# th.net
KiCad netlist of a schematic drawn in EAGLE
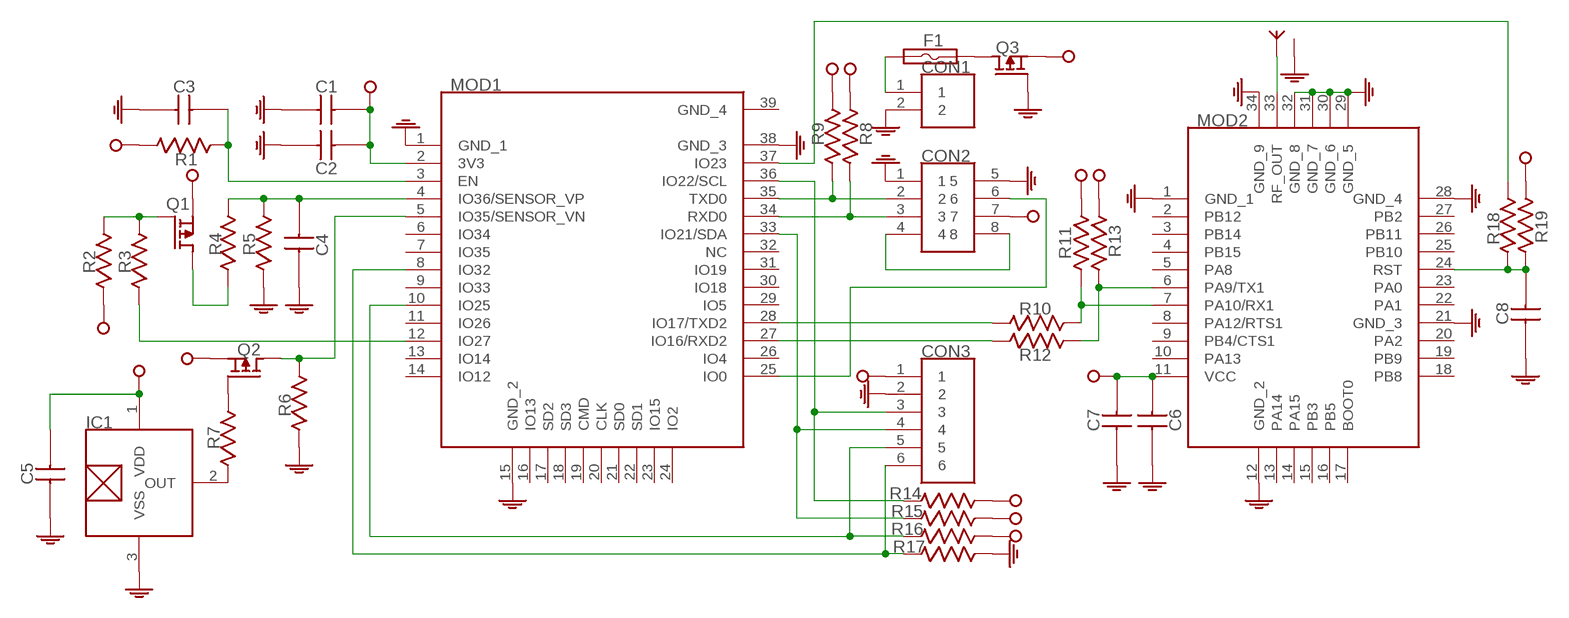
[diagram p0: schematic, sheet 1]

(export (version "E")
  (design (tool "Eeschema 10.0.6"))
  (components
    (comp (ref "ANT1")
      (value "SMA-RF")
      (footprint "eagle-import:SMA-RF")
      (libsource (lib "eagle-import") (part "SMA-RF"))
    )
    (comp (ref "C1")
      (value "CAPACITOR-0805")
      (footprint "eagle-import:0805")
      (libsource (lib "eagle-import") (part "CAPACITOR-0805"))
    )
    (comp (ref "C2")
      (value "CAPACITOR-0603")
      (footprint "eagle-import:0603")
      (libsource (lib "eagle-import") (part "CAPACITOR-0603"))
    )
    (comp (ref "C3")
      (value "CAPACITOR-0603")
      (footprint "eagle-import:0603")
      (libsource (lib "eagle-import") (part "CAPACITOR-0603"))
    )
    (comp (ref "C4")
      (value "CAPACITOR-0603")
      (footprint "eagle-import:0603")
      (libsource (lib "eagle-import") (part "CAPACITOR-0603"))
    )
    (comp (ref "C5")
      (value "CAPACITOR-0603")
      (footprint "eagle-import:0603")
      (libsource (lib "eagle-import") (part "CAPACITOR-0603"))
    )
    (comp (ref "C6")
      (value "CAPACITOR-0805")
      (footprint "eagle-import:0805")
      (libsource (lib "eagle-import") (part "CAPACITOR-0805"))
    )
    (comp (ref "C7")
      (value "CAPACITOR-0603")
      (footprint "eagle-import:0603")
      (libsource (lib "eagle-import") (part "CAPACITOR-0603"))
    )
    (comp (ref "C8")
      (value "CAPACITOR-0603")
      (footprint "eagle-import:0603")
      (libsource (lib "eagle-import") (part "CAPACITOR-0603"))
    )
    (comp (ref "CON1")
      (value "JST-PH-2-2.0MM")
      (footprint "eagle-import:JST-PH-2-2.0MM")
      (libsource (lib "eagle-import") (part "JST-PH-2-2.0MM"))
    )
    (comp (ref "CON2")
      (value "HEADER-8P-2R-DIP-2_0MM")
      (footprint "eagle-import:HEADER-8P-2R-DIP-2_0MM")
      (libsource (lib "eagle-import") (part "HEADER-8P-2R-DIP-2_0MM"))
    )
    (comp (ref "CON3")
      (value "CON-6P-3_81-PLUG")
      (footprint "eagle-import:CON-6P-3_81-PLUG")
      (libsource (lib "eagle-import") (part "CON-6P-3_81-PLUG"))
    )
    (comp (ref "F1")
      (value "FUSE-0805")
      (footprint "eagle-import:0805")
      (libsource (lib "eagle-import") (part "FUSE-0805"))
    )
    (comp (ref "IC1")
      (value "S-5712-SOT23-3")
      (footprint "eagle-import:SOT23-3")
      (libsource (lib "eagle-import") (part "S-5712-SOT23-3"))
    )
    (comp (ref "MOD1")
      (value "ESP32-WROOM-32D")
      (footprint "eagle-import:ESP32-WROOM-32D")
      (libsource (lib "eagle-import") (part "ESP32-WROOM-32D"))
    )
    (comp (ref "MOD2")
      (value "RAK811")
      (footprint "eagle-import:RAK811")
      (libsource (lib "eagle-import") (part "RAK811"))
    )
    (comp (ref "Q1")
      (value "P-MOSFET")
      (footprint "eagle-import:SOT23-3")
      (libsource (lib "eagle-import") (part "P-MOSFET"))
    )
    (comp (ref "Q2")
      (value "P-MOSFET")
      (footprint "eagle-import:SOT23-3")
      (libsource (lib "eagle-import") (part "P-MOSFET"))
    )
    (comp (ref "Q3")
      (value "P-MOSFET")
      (footprint "eagle-import:SOT23-3")
      (libsource (lib "eagle-import") (part "P-MOSFET"))
    )
    (comp (ref "R1")
      (value "RESISTOR-0603")
      (footprint "eagle-import:0603")
      (libsource (lib "eagle-import") (part "RESISTOR-0603"))
    )
    (comp (ref "R2")
      (value "RESISTOR-0603")
      (footprint "eagle-import:0603")
      (libsource (lib "eagle-import") (part "RESISTOR-0603"))
    )
    (comp (ref "R3")
      (value "RESISTOR-0603")
      (footprint "eagle-import:0603")
      (libsource (lib "eagle-import") (part "RESISTOR-0603"))
    )
    (comp (ref "R4")
      (value "RESISTOR-0603")
      (footprint "eagle-import:0603")
      (libsource (lib "eagle-import") (part "RESISTOR-0603"))
    )
    (comp (ref "R5")
      (value "RESISTOR-0603")
      (footprint "eagle-import:0603")
      (libsource (lib "eagle-import") (part "RESISTOR-0603"))
    )
    (comp (ref "R6")
      (value "RESISTOR-0603")
      (footprint "eagle-import:0603")
      (libsource (lib "eagle-import") (part "RESISTOR-0603"))
    )
    (comp (ref "R7")
      (value "RESISTOR-0603")
      (footprint "eagle-import:0603")
      (libsource (lib "eagle-import") (part "RESISTOR-0603"))
    )
    (comp (ref "R8")
      (value "RESISTOR-0603")
      (footprint "eagle-import:0603")
      (libsource (lib "eagle-import") (part "RESISTOR-0603"))
    )
    (comp (ref "R9")
      (value "RESISTOR-0603")
      (footprint "eagle-import:0603")
      (libsource (lib "eagle-import") (part "RESISTOR-0603"))
    )
    (comp (ref "R10")
      (value "RESISTOR-0603")
      (footprint "eagle-import:0603")
      (libsource (lib "eagle-import") (part "RESISTOR-0603"))
    )
    (comp (ref "R11")
      (value "RESISTOR-0603")
      (footprint "eagle-import:0603")
      (libsource (lib "eagle-import") (part "RESISTOR-0603"))
    )
    (comp (ref "R12")
      (value "RESISTOR-0603")
      (footprint "eagle-import:0603")
      (libsource (lib "eagle-import") (part "RESISTOR-0603"))
    )
    (comp (ref "R13")
      (value "RESISTOR-0603")
      (footprint "eagle-import:0603")
      (libsource (lib "eagle-import") (part "RESISTOR-0603"))
    )
    (comp (ref "R14")
      (value "RESISTOR-0603")
      (footprint "eagle-import:0603")
      (libsource (lib "eagle-import") (part "RESISTOR-0603"))
    )
    (comp (ref "R15")
      (value "RESISTOR-0603")
      (footprint "eagle-import:0603")
      (libsource (lib "eagle-import") (part "RESISTOR-0603"))
    )
    (comp (ref "R16")
      (value "RESISTOR-0603")
      (footprint "eagle-import:0603")
      (libsource (lib "eagle-import") (part "RESISTOR-0603"))
    )
    (comp (ref "R17")
      (value "RESISTOR-0603")
      (footprint "eagle-import:0603")
      (libsource (lib "eagle-import") (part "RESISTOR-0603"))
    )
    (comp (ref "R18")
      (value "RESISTOR-0603")
      (footprint "eagle-import:0603")
      (libsource (lib "eagle-import") (part "RESISTOR-0603"))
    )
    (comp (ref "R19")
      (value "RESISTOR-0603")
      (footprint "eagle-import:0603")
      (libsource (lib "eagle-import") (part "RESISTOR-0603"))
    )
  )
  (nets
    (net (code "1") (name "/GND_4") (class "Default")
      (node (ref "MOD1") (pin "39") (pinfunction "GND_4_39") (pintype "power_in"))
    )
    (net (code "2") (name "GND") (class "Default")
      (node (ref "ANT1") (pin "2") (pinfunction "GND_2") (pintype "power_in"))
      (node (ref "ANT1") (pin "3") (pinfunction "GND_3") (pintype "power_in"))
      (node (ref "ANT1") (pin "4") (pinfunction "GND_4") (pintype "power_in"))
      (node (ref "ANT1") (pin "5") (pinfunction "GND_5") (pintype "power_in"))
      (node (ref "C1") (pin "1") (pinfunction "1_1") (pintype "passive"))
      (node (ref "C2") (pin "1") (pinfunction "1_1") (pintype "passive"))
      (node (ref "C3") (pin "1") (pinfunction "1_1") (pintype "passive"))
      (node (ref "C4") (pin "1") (pinfunction "1_1") (pintype "passive"))
      (node (ref "C5") (pin "1") (pinfunction "1_1") (pintype "passive"))
      (node (ref "C6") (pin "1") (pinfunction "1_1") (pintype "passive"))
      (node (ref "C7") (pin "1") (pinfunction "1_1") (pintype "passive"))
      (node (ref "C8") (pin "1") (pinfunction "1_1") (pintype "passive"))
      (node (ref "CON1") (pin "2") (pinfunction "2_2") (pintype "bidirectional"))
      (node (ref "CON2") (pin "1") (pinfunction "1_1") (pintype "bidirectional"))
      (node (ref "CON2") (pin "5") (pinfunction "5_5") (pintype "bidirectional"))
      (node (ref "CON3") (pin "2") (pinfunction "2_2") (pintype "bidirectional"))
      (node (ref "IC1") (pin "3") (pinfunction "VSS_3") (pintype "power_in"))
      (node (ref "MOD1") (pin "1") (pinfunction "GND_1_1") (pintype "power_in"))
      (node (ref "MOD1") (pin "15") (pinfunction "GND_2_15") (pintype "power_in"))
      (node (ref "MOD1") (pin "38") (pinfunction "GND_3_38") (pintype "power_in"))
      (node (ref "MOD2") (pin "1") (pinfunction "GND_1_1") (pintype "power_in"))
      (node (ref "MOD2") (pin "12") (pinfunction "GND_2_12") (pintype "power_in"))
      (node (ref "MOD2") (pin "21") (pinfunction "GND_3_21") (pintype "power_in"))
      (node (ref "MOD2") (pin "28") (pinfunction "GND_4_28") (pintype "power_in"))
      (node (ref "MOD2") (pin "29") (pinfunction "GND_5_29") (pintype "power_in"))
      (node (ref "MOD2") (pin "30") (pinfunction "GND_6_30") (pintype "power_in"))
      (node (ref "MOD2") (pin "31") (pinfunction "GND_7_31") (pintype "power_in"))
      (node (ref "MOD2") (pin "32") (pinfunction "GND_8_32") (pintype "power_in"))
      (node (ref "MOD2") (pin "34") (pinfunction "GND_9_34") (pintype "power_in"))
      (node (ref "Q3") (pin "1") (pinfunction "G_1") (pintype "bidirectional"))
      (node (ref "R17") (pin "2") (pinfunction "2_2") (pintype "passive"))
      (node (ref "R5") (pin "1") (pinfunction "1_1") (pintype "passive"))
      (node (ref "R6") (pin "1") (pinfunction "1_1") (pintype "passive"))
    )
    (net (code "3") (name "Net-(ANT1-ANT)") (class "Default")
      (node (ref "ANT1") (pin "1") (pinfunction "ANT_1") (pintype "bidirectional"))
      (node (ref "MOD2") (pin "33") (pinfunction "RF_OUT_33") (pintype "bidirectional"))
    )
    (net (code "4") (name "Net-(CON1-Pad1)") (class "Default")
      (node (ref "CON1") (pin "1") (pinfunction "1_1") (pintype "bidirectional"))
      (node (ref "F1") (pin "1") (pinfunction "1_1") (pintype "passive"))
    )
    (net (code "5") (name "Net-(CON2-Pad4)") (class "Default")
      (node (ref "CON2") (pin "4") (pinfunction "4_4") (pintype "bidirectional"))
      (node (ref "CON2") (pin "8") (pinfunction "8_8") (pintype "bidirectional"))
    )
    (net (code "6") (name "Net-(IC1-OUT)") (class "Default")
      (node (ref "IC1") (pin "2") (pinfunction "OUT_2") (pintype "bidirectional"))
      (node (ref "R7") (pin "1") (pinfunction "1_1") (pintype "passive"))
    )
    (net (code "7") (name "Net-(MOD1-EN)") (class "Default")
      (node (ref "C3") (pin "2") (pinfunction "2_2") (pintype "passive"))
      (node (ref "MOD1") (pin "3") (pinfunction "EN_3") (pintype "bidirectional"))
      (node (ref "R1") (pin "2") (pinfunction "2_2") (pintype "passive"))
    )
    (net (code "8") (name "Net-(MOD1-IO0)") (class "Default")
      (node (ref "CON2") (pin "6") (pinfunction "6_6") (pintype "bidirectional"))
      (node (ref "MOD1") (pin "25") (pinfunction "IO0_25") (pintype "bidirectional"))
    )
    (net (code "9") (name "Net-(MOD1-IO16{slash}RXD2)") (class "Default")
      (node (ref "MOD1") (pin "27") (pinfunction "IO16/RXD2_27") (pintype "bidirectional"))
      (node (ref "R12") (pin "1") (pinfunction "1_1") (pintype "passive"))
    )
    (net (code "10") (name "Net-(MOD1-IO17{slash}TXD2)") (class "Default")
      (node (ref "MOD1") (pin "28") (pinfunction "IO17/TXD2_28") (pintype "bidirectional"))
      (node (ref "R10") (pin "1") (pinfunction "1_1") (pintype "passive"))
    )
    (net (code "11") (name "Net-(MOD1-IO21{slash}SDA)") (class "Default")
      (node (ref "CON3") (pin "4") (pinfunction "4_4") (pintype "bidirectional"))
      (node (ref "MOD1") (pin "33") (pinfunction "IO21/SDA_33") (pintype "bidirectional"))
      (node (ref "R15") (pin "1") (pinfunction "1_1") (pintype "passive"))
    )
    (net (code "12") (name "Net-(MOD1-IO22{slash}SCL)") (class "Default")
      (node (ref "CON3") (pin "3") (pinfunction "3_3") (pintype "bidirectional"))
      (node (ref "MOD1") (pin "36") (pinfunction "IO22/SCL_36") (pintype "bidirectional"))
      (node (ref "R14") (pin "1") (pinfunction "1_1") (pintype "passive"))
    )
    (net (code "13") (name "Net-(MOD1-IO23)") (class "Default")
      (node (ref "MOD1") (pin "37") (pinfunction "IO23_37") (pintype "bidirectional"))
      (node (ref "R18") (pin "2") (pinfunction "2_2") (pintype "passive"))
    )
    (net (code "14") (name "Net-(MOD1-IO25)") (class "Default")
      (node (ref "CON3") (pin "5") (pinfunction "5_5") (pintype "bidirectional"))
      (node (ref "MOD1") (pin "10") (pinfunction "IO25_10") (pintype "bidirectional"))
      (node (ref "R16") (pin "1") (pinfunction "1_1") (pintype "passive"))
    )
    (net (code "15") (name "Net-(MOD1-IO27)") (class "Default")
      (node (ref "MOD1") (pin "12") (pinfunction "IO27_12") (pintype "bidirectional"))
      (node (ref "R3") (pin "1") (pinfunction "1_1") (pintype "passive"))
    )
    (net (code "16") (name "Net-(MOD1-IO32)") (class "Default")
      (node (ref "CON3") (pin "6") (pinfunction "6_6") (pintype "bidirectional"))
      (node (ref "MOD1") (pin "8") (pinfunction "IO32_8") (pintype "bidirectional"))
      (node (ref "R17") (pin "1") (pinfunction "1_1") (pintype "passive"))
    )
    (net (code "17") (name "Net-(MOD1-IO35{slash}SENSOR_VN)") (class "Default")
      (node (ref "MOD1") (pin "5") (pinfunction "IO35/SENSOR_VN_5") (pintype "bidirectional"))
      (node (ref "Q2") (pin "3") (pinfunction "D_3") (pintype "bidirectional"))
      (node (ref "R6") (pin "2") (pinfunction "2_2") (pintype "passive"))
    )
    (net (code "18") (name "Net-(MOD1-IO36{slash}SENSOR_VP)") (class "Default")
      (node (ref "C4") (pin "2") (pinfunction "2_2") (pintype "passive"))
      (node (ref "MOD1") (pin "4") (pinfunction "IO36/SENSOR_VP_4") (pintype "bidirectional"))
      (node (ref "R4") (pin "2") (pinfunction "2_2") (pintype "passive"))
      (node (ref "R5") (pin "2") (pinfunction "2_2") (pintype "passive"))
    )
    (net (code "19") (name "Net-(MOD1-RXD0)") (class "Default")
      (node (ref "CON2") (pin "3") (pinfunction "3_3") (pintype "bidirectional"))
      (node (ref "MOD1") (pin "34") (pinfunction "RXD0_34") (pintype "bidirectional"))
      (node (ref "R8") (pin "1") (pinfunction "1_1") (pintype "passive"))
    )
    (net (code "20") (name "Net-(MOD1-TXD0)") (class "Default")
      (node (ref "CON2") (pin "2") (pinfunction "2_2") (pintype "bidirectional"))
      (node (ref "MOD1") (pin "35") (pinfunction "TXD0_35") (pintype "bidirectional"))
      (node (ref "R9") (pin "1") (pinfunction "1_1") (pintype "passive"))
    )
    (net (code "21") (name "Net-(MOD2-PA9{slash}TX1)") (class "Default")
      (node (ref "MOD2") (pin "6") (pinfunction "PA9/TX1_6") (pintype "bidirectional"))
      (node (ref "R12") (pin "2") (pinfunction "2_2") (pintype "passive"))
      (node (ref "R13") (pin "2") (pinfunction "2_2") (pintype "passive"))
    )
    (net (code "22") (name "Net-(MOD2-PA10{slash}RX1)") (class "Default")
      (node (ref "MOD2") (pin "7") (pinfunction "PA10/RX1_7") (pintype "bidirectional"))
      (node (ref "R10") (pin "2") (pinfunction "2_2") (pintype "passive"))
      (node (ref "R11") (pin "2") (pinfunction "2_2") (pintype "passive"))
    )
    (net (code "23") (name "Net-(MOD2-RST)") (class "Default")
      (node (ref "C8") (pin "2") (pinfunction "2_2") (pintype "passive"))
      (node (ref "MOD2") (pin "24") (pinfunction "RST_24") (pintype "bidirectional"))
      (node (ref "R18") (pin "1") (pinfunction "1_1") (pintype "passive"))
      (node (ref "R19") (pin "1") (pinfunction "1_1") (pintype "passive"))
    )
    (net (code "24") (name "Net-(Q1-D)") (class "Default")
      (node (ref "Q1") (pin "3") (pinfunction "D_3") (pintype "bidirectional"))
      (node (ref "R4") (pin "1") (pinfunction "1_1") (pintype "passive"))
    )
    (net (code "25") (name "Net-(Q1-G)") (class "Default")
      (node (ref "Q1") (pin "1") (pinfunction "G_1") (pintype "bidirectional"))
      (node (ref "R2") (pin "2") (pinfunction "2_2") (pintype "passive"))
      (node (ref "R3") (pin "2") (pinfunction "2_2") (pintype "passive"))
    )
    (net (code "26") (name "Net-(Q2-G)") (class "Default")
      (node (ref "Q2") (pin "1") (pinfunction "G_1") (pintype "bidirectional"))
      (node (ref "R7") (pin "2") (pinfunction "2_2") (pintype "passive"))
    )
    (net (code "27") (name "Net-(Q3-D)") (class "Default")
      (node (ref "F1") (pin "2") (pinfunction "2_2") (pintype "passive"))
      (node (ref "Q3") (pin "3") (pinfunction "D_3") (pintype "bidirectional"))
    )
    (net (code "28") (name "VCC") (class "Default")
      (node (ref "C1") (pin "2") (pinfunction "2_2") (pintype "passive"))
      (node (ref "C2") (pin "2") (pinfunction "2_2") (pintype "passive"))
      (node (ref "C5") (pin "2") (pinfunction "2_2") (pintype "passive"))
      (node (ref "C6") (pin "2") (pinfunction "2_2") (pintype "passive"))
      (node (ref "C7") (pin "2") (pinfunction "2_2") (pintype "passive"))
      (node (ref "CON2") (pin "7") (pinfunction "7_7") (pintype "bidirectional"))
      (node (ref "CON3") (pin "1") (pinfunction "1_1") (pintype "bidirectional"))
      (node (ref "IC1") (pin "1") (pinfunction "VDD_1") (pintype "power_in"))
      (node (ref "MOD1") (pin "2") (pinfunction "3V3_2") (pintype "power_in"))
      (node (ref "MOD2") (pin "11") (pinfunction "VCC_11") (pintype "power_in"))
      (node (ref "Q1") (pin "2") (pinfunction "S_2") (pintype "bidirectional"))
      (node (ref "Q2") (pin "2") (pinfunction "S_2") (pintype "bidirectional"))
      (node (ref "Q3") (pin "2") (pinfunction "S_2") (pintype "bidirectional"))
      (node (ref "R1") (pin "1") (pinfunction "1_1") (pintype "passive"))
      (node (ref "R11") (pin "1") (pinfunction "1_1") (pintype "passive"))
      (node (ref "R13") (pin "1") (pinfunction "1_1") (pintype "passive"))
      (node (ref "R14") (pin "2") (pinfunction "2_2") (pintype "passive"))
      (node (ref "R15") (pin "2") (pinfunction "2_2") (pintype "passive"))
      (node (ref "R16") (pin "2") (pinfunction "2_2") (pintype "passive"))
      (node (ref "R19") (pin "2") (pinfunction "2_2") (pintype "passive"))
      (node (ref "R2") (pin "1") (pinfunction "1_1") (pintype "passive"))
      (node (ref "R8") (pin "2") (pinfunction "2_2") (pintype "passive"))
      (node (ref "R9") (pin "2") (pinfunction "2_2") (pintype "passive"))
    )
    (net (code "29") (name "unconnected-(MOD1-CLK-Pad20)") (class "Default")
      (node (ref "MOD1") (pin "20") (pinfunction "CLK_20") (pintype "bidirectional"))
    )
    (net (code "30") (name "unconnected-(MOD1-CMD-Pad19)") (class "Default")
      (node (ref "MOD1") (pin "19") (pinfunction "CMD_19") (pintype "bidirectional"))
    )
    (net (code "31") (name "unconnected-(MOD1-IO2-Pad24)") (class "Default")
      (node (ref "MOD1") (pin "24") (pinfunction "IO2_24") (pintype "bidirectional"))
    )
    (net (code "32") (name "unconnected-(MOD1-IO4-Pad26)") (class "Default")
      (node (ref "MOD1") (pin "26") (pinfunction "IO4_26") (pintype "bidirectional"))
    )
    (net (code "33") (name "unconnected-(MOD1-IO5-Pad29)") (class "Default")
      (node (ref "MOD1") (pin "29") (pinfunction "IO5_29") (pintype "bidirectional"))
    )
    (net (code "34") (name "unconnected-(MOD1-IO12-Pad14)") (class "Default")
      (node (ref "MOD1") (pin "14") (pinfunction "IO12_14") (pintype "bidirectional"))
    )
    (net (code "35") (name "unconnected-(MOD1-IO13-Pad16)") (class "Default")
      (node (ref "MOD1") (pin "16") (pinfunction "IO13_16") (pintype "bidirectional"))
    )
    (net (code "36") (name "unconnected-(MOD1-IO14-Pad13)") (class "Default")
      (node (ref "MOD1") (pin "13") (pinfunction "IO14_13") (pintype "bidirectional"))
    )
    (net (code "37") (name "unconnected-(MOD1-IO15-Pad23)") (class "Default")
      (node (ref "MOD1") (pin "23") (pinfunction "IO15_23") (pintype "bidirectional"))
    )
    (net (code "38") (name "unconnected-(MOD1-IO18-Pad30)") (class "Default")
      (node (ref "MOD1") (pin "30") (pinfunction "IO18_30") (pintype "bidirectional"))
    )
    (net (code "39") (name "unconnected-(MOD1-IO19-Pad31)") (class "Default")
      (node (ref "MOD1") (pin "31") (pinfunction "IO19_31") (pintype "bidirectional"))
    )
    (net (code "40") (name "unconnected-(MOD1-IO26-Pad11)") (class "Default")
      (node (ref "MOD1") (pin "11") (pinfunction "IO26_11") (pintype "bidirectional"))
    )
    (net (code "41") (name "unconnected-(MOD1-IO33-Pad9)") (class "Default")
      (node (ref "MOD1") (pin "9") (pinfunction "IO33_9") (pintype "bidirectional"))
    )
    (net (code "42") (name "unconnected-(MOD1-IO34-Pad6)") (class "Default")
      (node (ref "MOD1") (pin "6") (pinfunction "IO34_6") (pintype "bidirectional"))
    )
    (net (code "43") (name "unconnected-(MOD1-IO35-Pad7)") (class "Default")
      (node (ref "MOD1") (pin "7") (pinfunction "IO35_7") (pintype "bidirectional"))
    )
    (net (code "44") (name "unconnected-(MOD1-NC-Pad32)") (class "Default")
      (node (ref "MOD1") (pin "32") (pinfunction "NC_32") (pintype "no_connect"))
    )
    (net (code "45") (name "unconnected-(MOD1-SD0-Pad21)") (class "Default")
      (node (ref "MOD1") (pin "21") (pinfunction "SD0_21") (pintype "bidirectional"))
    )
    (net (code "46") (name "unconnected-(MOD1-SD1-Pad22)") (class "Default")
      (node (ref "MOD1") (pin "22") (pinfunction "SD1_22") (pintype "bidirectional"))
    )
    (net (code "47") (name "unconnected-(MOD1-SD2-Pad17)") (class "Default")
      (node (ref "MOD1") (pin "17") (pinfunction "SD2_17") (pintype "bidirectional"))
    )
    (net (code "48") (name "unconnected-(MOD1-SD3-Pad18)") (class "Default")
      (node (ref "MOD1") (pin "18") (pinfunction "SD3_18") (pintype "bidirectional"))
    )
    (net (code "49") (name "unconnected-(MOD2-BOOT0-Pad17)") (class "Default")
      (node (ref "MOD2") (pin "17") (pinfunction "BOOT0_17") (pintype "bidirectional"))
    )
    (net (code "50") (name "unconnected-(MOD2-PA0-Pad23)") (class "Default")
      (node (ref "MOD2") (pin "23") (pinfunction "PA0_23") (pintype "bidirectional"))
    )
    (net (code "51") (name "unconnected-(MOD2-PA1-Pad22)") (class "Default")
      (node (ref "MOD2") (pin "22") (pinfunction "PA1_22") (pintype "bidirectional"))
    )
    (net (code "52") (name "unconnected-(MOD2-PA2-Pad20)") (class "Default")
      (node (ref "MOD2") (pin "20") (pinfunction "PA2_20") (pintype "bidirectional"))
    )
    (net (code "53") (name "unconnected-(MOD2-PA8-Pad5)") (class "Default")
      (node (ref "MOD2") (pin "5") (pinfunction "PA8_5") (pintype "bidirectional"))
    )
    (net (code "54") (name "unconnected-(MOD2-PA12{slash}RTS1-Pad8)") (class "Default")
      (node (ref "MOD2") (pin "8") (pinfunction "PA12/RTS1_8") (pintype "bidirectional"))
    )
    (net (code "55") (name "unconnected-(MOD2-PA13-Pad10)") (class "Default")
      (node (ref "MOD2") (pin "10") (pinfunction "PA13_10") (pintype "bidirectional"))
    )
    (net (code "56") (name "unconnected-(MOD2-PA14-Pad13)") (class "Default")
      (node (ref "MOD2") (pin "13") (pinfunction "PA14_13") (pintype "bidirectional"))
    )
    (net (code "57") (name "unconnected-(MOD2-PA15-Pad14)") (class "Default")
      (node (ref "MOD2") (pin "14") (pinfunction "PA15_14") (pintype "bidirectional"))
    )
    (net (code "58") (name "unconnected-(MOD2-PB2-Pad27)") (class "Default")
      (node (ref "MOD2") (pin "27") (pinfunction "PB2_27") (pintype "bidirectional"))
    )
    (net (code "59") (name "unconnected-(MOD2-PB3-Pad15)") (class "Default")
      (node (ref "MOD2") (pin "15") (pinfunction "PB3_15") (pintype "bidirectional"))
    )
    (net (code "60") (name "unconnected-(MOD2-PB4{slash}CTS1-Pad9)") (class "Default")
      (node (ref "MOD2") (pin "9") (pinfunction "PB4/CTS1_9") (pintype "bidirectional"))
    )
    (net (code "61") (name "unconnected-(MOD2-PB5-Pad16)") (class "Default")
      (node (ref "MOD2") (pin "16") (pinfunction "PB5_16") (pintype "bidirectional"))
    )
    (net (code "62") (name "unconnected-(MOD2-PB8-Pad18)") (class "Default")
      (node (ref "MOD2") (pin "18") (pinfunction "PB8_18") (pintype "bidirectional"))
    )
    (net (code "63") (name "unconnected-(MOD2-PB9-Pad19)") (class "Default")
      (node (ref "MOD2") (pin "19") (pinfunction "PB9_19") (pintype "bidirectional"))
    )
    (net (code "64") (name "unconnected-(MOD2-PB10-Pad25)") (class "Default")
      (node (ref "MOD2") (pin "25") (pinfunction "PB10_25") (pintype "bidirectional"))
    )
    (net (code "65") (name "unconnected-(MOD2-PB11-Pad26)") (class "Default")
      (node (ref "MOD2") (pin "26") (pinfunction "PB11_26") (pintype "bidirectional"))
    )
    (net (code "66") (name "unconnected-(MOD2-PB12-Pad2)") (class "Default")
      (node (ref "MOD2") (pin "2") (pinfunction "PB12_2") (pintype "bidirectional"))
    )
    (net (code "67") (name "unconnected-(MOD2-PB14-Pad3)") (class "Default")
      (node (ref "MOD2") (pin "3") (pinfunction "PB14_3") (pintype "bidirectional"))
    )
    (net (code "68") (name "unconnected-(MOD2-PB15-Pad4)") (class "Default")
      (node (ref "MOD2") (pin "4") (pinfunction "PB15_4") (pintype "bidirectional"))
    )
  )
)
